# DCmixer.net
KiCad netlist of a schematic drawn in EAGLE
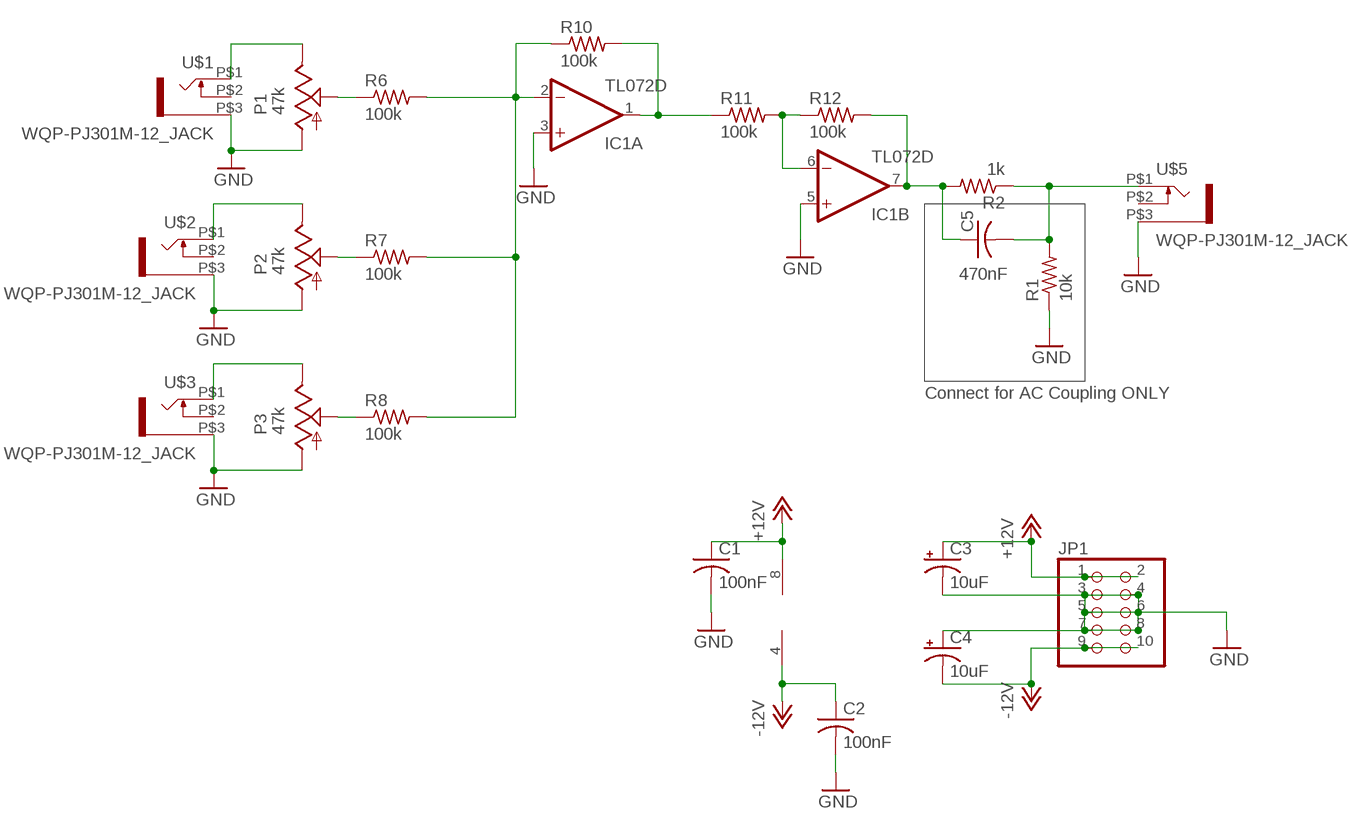
[diagram p0: schematic, sheet 1]

(export (version "E")
  (design (tool "Eeschema 10.0.6"))
  (components
    (comp (ref "C1")
      (value "100nF")
      (footprint "eagle-import:C0603K")
      (libsource (lib "eagle-import") (part "C-USC0603K"))
    )
    (comp (ref "C2")
      (value "100nF")
      (footprint "eagle-import:C0603K")
      (libsource (lib "eagle-import") (part "C-USC0603K"))
    )
    (comp (ref "C3")
      (value "10uF")
      (footprint "eagle-import:E2-5")
      (libsource (lib "eagle-import") (part "CPOL-USE2-5"))
    )
    (comp (ref "C4")
      (value "10uF")
      (footprint "eagle-import:E2-5")
      (libsource (lib "eagle-import") (part "CPOL-USE2-5"))
    )
    (comp (ref "C5")
      (value "470nF")
      (footprint "eagle-import:C0603K")
      (libsource (lib "eagle-import") (part "C-USC0603K"))
    )
    (comp (ref "IC1")
      (value "TL072D")
      (footprint "eagle-import:SO08")
      (libsource (lib "eagle-import") (part "TL072D"))
    )
    (comp (ref "JP1")
      (value "PINHD-2X5")
      (footprint "eagle-import:2X05")
      (libsource (lib "eagle-import") (part "PINHD-2X5"))
    )
    (comp (ref "P1")
      (value "47k")
      (footprint "eagle-import:EVUF")
      (libsource (lib "eagle-import") (part "US-EVUAF2"))
    )
    (comp (ref "P2")
      (value "47k")
      (footprint "eagle-import:EVUF")
      (libsource (lib "eagle-import") (part "US-EVUAF2"))
    )
    (comp (ref "P3")
      (value "47k")
      (footprint "eagle-import:EVUF")
      (libsource (lib "eagle-import") (part "US-EVUAF2"))
    )
    (comp (ref "R1")
      (value "10k")
      (footprint "eagle-import:R0603")
      (libsource (lib "eagle-import") (part "R-US_R0603"))
    )
    (comp (ref "R2")
      (value "1k")
      (footprint "eagle-import:R0603")
      (libsource (lib "eagle-import") (part "R-US_R0603"))
    )
    (comp (ref "R6")
      (value "100k")
      (footprint "eagle-import:R0603")
      (libsource (lib "eagle-import") (part "R-US_R0603"))
    )
    (comp (ref "R7")
      (value "100k")
      (footprint "eagle-import:R0603")
      (libsource (lib "eagle-import") (part "R-US_R0603"))
    )
    (comp (ref "R8")
      (value "100k")
      (footprint "eagle-import:R0603")
      (libsource (lib "eagle-import") (part "R-US_R0603"))
    )
    (comp (ref "R10")
      (value "100k")
      (footprint "eagle-import:R0603")
      (libsource (lib "eagle-import") (part "R-US_R0603"))
    )
    (comp (ref "R11")
      (value "100k")
      (footprint "eagle-import:R0603")
      (libsource (lib "eagle-import") (part "R-US_R0603"))
    )
    (comp (ref "R12")
      (value "100k")
      (footprint "eagle-import:R0603")
      (libsource (lib "eagle-import") (part "R-US_R0603"))
    )
    (comp (ref "U$1")
      (value "WQP-PJ301M-12_JACK")
      (footprint "eagle-import:WQP-PJ301M-12_JACK")
      (libsource (lib "eagle-import") (part "WQP-PJ301M-12_JACK"))
    )
    (comp (ref "U$2")
      (value "WQP-PJ301M-12_JACK")
      (footprint "eagle-import:WQP-PJ301M-12_JACK")
      (libsource (lib "eagle-import") (part "WQP-PJ301M-12_JACK"))
    )
    (comp (ref "U$3")
      (value "WQP-PJ301M-12_JACK")
      (footprint "eagle-import:WQP-PJ301M-12_JACK")
      (libsource (lib "eagle-import") (part "WQP-PJ301M-12_JACK"))
    )
    (comp (ref "U$5")
      (value "WQP-PJ301M-12_JACK")
      (footprint "eagle-import:WQP-PJ301M-12_JACK")
      (libsource (lib "eagle-import") (part "WQP-PJ301M-12_JACK"))
    )
  )
  (nets
    (net (code "1") (name "+12V") (class "Default")
      (node (ref "C1") (pin "1") (pinfunction "1_1") (pintype "passive"))
      (node (ref "C3") (pin "+") (pinfunction "+_+") (pintype "passive"))
      (node (ref "IC1") (pin "8") (pinfunction "V+_8") (pintype "power_in"))
      (node (ref "JP1") (pin "1") (pinfunction "1_1") (pintype "passive"))
      (node (ref "JP1") (pin "2") (pinfunction "2_2") (pintype "passive"))
    )
    (net (code "2") (name "-12V") (class "Default")
      (node (ref "C2") (pin "1") (pinfunction "1_1") (pintype "passive"))
      (node (ref "C4") (pin "-") (pinfunction "-_-") (pintype "passive"))
      (node (ref "IC1") (pin "4") (pinfunction "V-_4") (pintype "power_in"))
      (node (ref "JP1") (pin "10") (pinfunction "10_10") (pintype "passive"))
      (node (ref "JP1") (pin "9") (pinfunction "9_9") (pintype "passive"))
    )
    (net (code "3") (name "GND") (class "Default")
      (node (ref "C1") (pin "2") (pinfunction "2_2") (pintype "passive"))
      (node (ref "C2") (pin "2") (pinfunction "2_2") (pintype "passive"))
      (node (ref "C3") (pin "-") (pinfunction "-_-") (pintype "passive"))
      (node (ref "C4") (pin "+") (pinfunction "+_+") (pintype "passive"))
      (node (ref "IC1") (pin "3") (pinfunction "+IN_3") (pintype "input"))
      (node (ref "IC1") (pin "5") (pinfunction "+IN_5") (pintype "input"))
      (node (ref "JP1") (pin "3") (pinfunction "3_3") (pintype "passive"))
      (node (ref "JP1") (pin "4") (pinfunction "4_4") (pintype "passive"))
      (node (ref "JP1") (pin "5") (pinfunction "5_5") (pintype "passive"))
      (node (ref "JP1") (pin "6") (pinfunction "6_6") (pintype "passive"))
      (node (ref "JP1") (pin "7") (pinfunction "7_7") (pintype "passive"))
      (node (ref "JP1") (pin "8") (pinfunction "8_8") (pintype "passive"))
      (node (ref "P1") (pin "1") (pinfunction "A_1") (pintype "passive"))
      (node (ref "P2") (pin "1") (pinfunction "A_1") (pintype "passive"))
      (node (ref "P3") (pin "1") (pinfunction "A_1") (pintype "passive"))
      (node (ref "R1") (pin "1") (pinfunction "1_1") (pintype "passive"))
      (node (ref "U$1") (pin "P$3") (pinfunction "1_P$3") (pintype "passive"))
      (node (ref "U$2") (pin "P$3") (pinfunction "1_P$3") (pintype "passive"))
      (node (ref "U$3") (pin "P$3") (pinfunction "1_P$3") (pintype "passive"))
      (node (ref "U$5") (pin "P$3") (pinfunction "1_P$3") (pintype "passive"))
    )
    (net (code "4") (name "Net-(IC1A--IN)") (class "Default")
      (node (ref "IC1") (pin "2") (pinfunction "-IN_2") (pintype "input"))
      (node (ref "R10") (pin "1") (pinfunction "1_1") (pintype "passive"))
      (node (ref "R6") (pin "2") (pinfunction "2_2") (pintype "passive"))
      (node (ref "R7") (pin "2") (pinfunction "2_2") (pintype "passive"))
      (node (ref "R8") (pin "2") (pinfunction "2_2") (pintype "passive"))
    )
    (net (code "5") (name "Net-(IC1A-OUT)") (class "Default")
      (node (ref "IC1") (pin "1") (pinfunction "OUT_1") (pintype "output"))
      (node (ref "R10") (pin "2") (pinfunction "2_2") (pintype "passive"))
      (node (ref "R11") (pin "1") (pinfunction "1_1") (pintype "passive"))
    )
    (net (code "6") (name "Net-(IC1B--IN)") (class "Default")
      (node (ref "IC1") (pin "6") (pinfunction "-IN_6") (pintype "input"))
      (node (ref "R11") (pin "2") (pinfunction "2_2") (pintype "passive"))
      (node (ref "R12") (pin "1") (pinfunction "1_1") (pintype "passive"))
    )
    (net (code "7") (name "Net-(IC1B-OUT)") (class "Default")
      (node (ref "C5") (pin "1") (pinfunction "1_1") (pintype "passive"))
      (node (ref "IC1") (pin "7") (pinfunction "OUT_7") (pintype "output"))
      (node (ref "R12") (pin "2") (pinfunction "2_2") (pintype "passive"))
      (node (ref "R2") (pin "2") (pinfunction "2_2") (pintype "passive"))
    )
    (net (code "8") (name "Net-(P1-E)") (class "Default")
      (node (ref "P1") (pin "3") (pinfunction "E_3") (pintype "passive"))
      (node (ref "U$1") (pin "P$1") (pinfunction "2_P$1") (pintype "passive"))
    )
    (net (code "9") (name "Net-(P1-S)") (class "Default")
      (node (ref "P1") (pin "2") (pinfunction "S_2") (pintype "passive"))
      (node (ref "R6") (pin "1") (pinfunction "1_1") (pintype "passive"))
    )
    (net (code "10") (name "Net-(P2-E)") (class "Default")
      (node (ref "P2") (pin "3") (pinfunction "E_3") (pintype "passive"))
      (node (ref "U$2") (pin "P$1") (pinfunction "2_P$1") (pintype "passive"))
    )
    (net (code "11") (name "Net-(P2-S)") (class "Default")
      (node (ref "P2") (pin "2") (pinfunction "S_2") (pintype "passive"))
      (node (ref "R7") (pin "1") (pinfunction "1_1") (pintype "passive"))
    )
    (net (code "12") (name "Net-(P3-E)") (class "Default")
      (node (ref "P3") (pin "3") (pinfunction "E_3") (pintype "passive"))
      (node (ref "U$3") (pin "P$1") (pinfunction "2_P$1") (pintype "passive"))
    )
    (net (code "13") (name "Net-(P3-S)") (class "Default")
      (node (ref "P3") (pin "2") (pinfunction "S_2") (pintype "passive"))
      (node (ref "R8") (pin "1") (pinfunction "1_1") (pintype "passive"))
    )
    (net (code "14") (name "Net-(U$5-2)") (class "Default")
      (node (ref "C5") (pin "2") (pinfunction "2_2") (pintype "passive"))
      (node (ref "R1") (pin "2") (pinfunction "2_2") (pintype "passive"))
      (node (ref "R2") (pin "1") (pinfunction "1_1") (pintype "passive"))
      (node (ref "U$5") (pin "P$1") (pinfunction "2_P$1") (pintype "passive"))
    )
    (net (code "15") (name "unconnected-(U$1-3-PadP$2)") (class "Default")
      (node (ref "U$1") (pin "P$2") (pinfunction "3_P$2") (pintype "passive"))
    )
    (net (code "16") (name "unconnected-(U$2-3-PadP$2)") (class "Default")
      (node (ref "U$2") (pin "P$2") (pinfunction "3_P$2") (pintype "passive"))
    )
    (net (code "17") (name "unconnected-(U$3-3-PadP$2)") (class "Default")
      (node (ref "U$3") (pin "P$2") (pinfunction "3_P$2") (pintype "passive"))
    )
    (net (code "18") (name "unconnected-(U$5-3-PadP$2)") (class "Default")
      (node (ref "U$5") (pin "P$2") (pinfunction "3_P$2") (pintype "passive"))
    )
  )
)
